# R3Mkr12F_MB.net
KiCad netlist of a schematic drawn in EAGLE
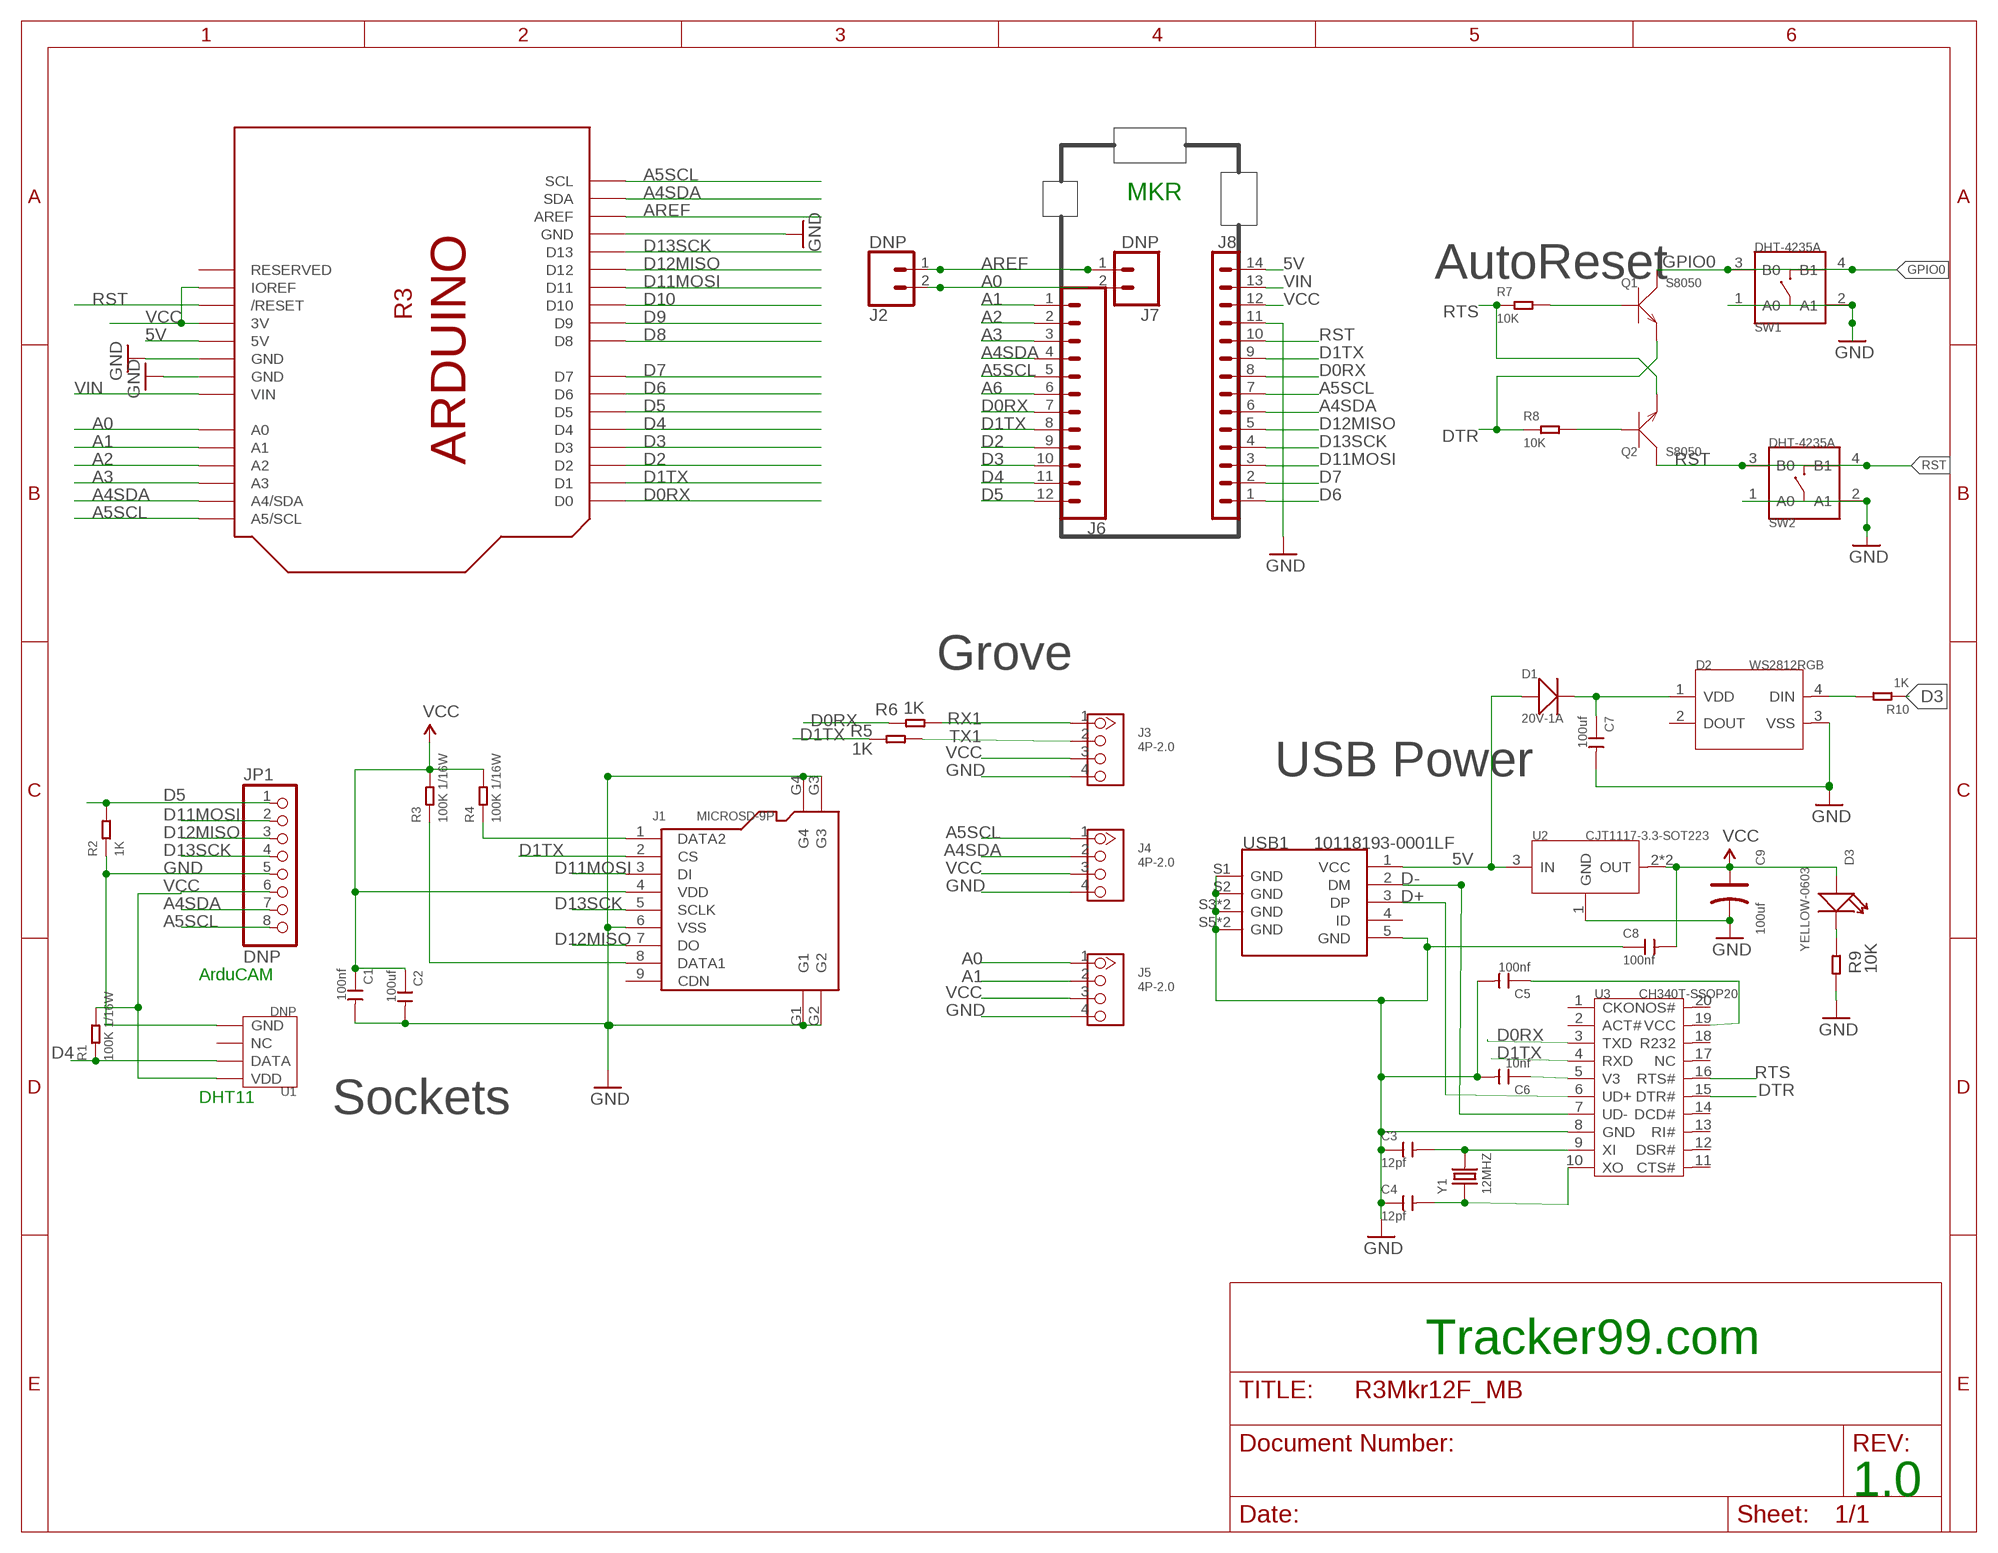
[diagram p0: schematic, sheet 1]

(export (version "E")
  (design (tool "Eeschema 10.0.6"))
  (components
    (comp (ref "C1")
      (value "100nf")
      (footprint "eagle-import:C0603")
      (fields (field (name "MPN") "CC0603KRX7R9BB104"))
      (libsource (lib "eagle-import") (part "CERAMIC-100NF-50V-10%-X7R(0603)"))
    )
    (comp (ref "C2")
      (value "100uf")
      (footprint "eagle-import:C1206")
      (fields (field (name "MPN") "GRM31CR60J107ME39L"))
      (libsource (lib "eagle-import") (part "CERAMIC-100UF-6.3V-20%-X5R(1206)"))
    )
    (comp (ref "C3")
      (value "12pf")
      (footprint "eagle-import:C0402")
      (fields (field (name "MPN") "CC0402JRNPO9BN120"))
      (libsource (lib "eagle-import") (part "CERAMIC-12PF-50V-5%-NPO(0402)"))
    )
    (comp (ref "C4")
      (value "12pf")
      (footprint "eagle-import:C0402")
      (fields (field (name "MPN") "CC0402JRNPO9BN120"))
      (libsource (lib "eagle-import") (part "CERAMIC-12PF-50V-5%-NPO(0402)"))
    )
    (comp (ref "C5")
      (value "100nf")
      (footprint "eagle-import:C0603")
      (fields (field (name "MPN") "CC0603KRX7R9BB104"))
      (libsource (lib "eagle-import") (part "CERAMIC-100NF-50V-10%-X7R(0603)"))
    )
    (comp (ref "C6")
      (value "10nf")
      (footprint "eagle-import:C0603")
      (fields (field (name "MPN") "CC0603KRX7R9BB103"))
      (libsource (lib "eagle-import") (part "CERAMIC-10NF-50V-10%-X7R(0603)"))
    )
    (comp (ref "C7")
      (value "100uf")
      (footprint "eagle-import:C1206")
      (fields (field (name "MPN") "GRM31CR60J107ME39L"))
      (libsource (lib "eagle-import") (part "CERAMIC-100UF-6.3V-20%-X5R(1206)"))
    )
    (comp (ref "C8")
      (value "100nf")
      (footprint "eagle-import:C0603")
      (fields (field (name "MPN") "CC0603KRX7R9BB104"))
      (libsource (lib "eagle-import") (part "CERAMIC-100NF-50V-10%-X7R(0603)"))
    )
    (comp (ref "C9")
      (value "100uf")
      (footprint "eagle-import:AVX-B")
      (fields (field (name "MPN") "TAJB107M010#NJ"))
      (libsource (lib "eagle-import") (part "TANTALUM-SMD-100UF-10V(AVX-B)"))
    )
    (comp (ref "D1")
      (value "20V-1A")
      (footprint "eagle-import:SOD-123")
      (fields (field (name "MPN") "B5819W"))
      (libsource (lib "eagle-import") (part "SMD-DIODE-SCHOTTKY-20V-1A(SOD-123)"))
    )
    (comp (ref "D2")
      (value "WS2812RGB")
      (footprint "eagle-import:LED4-SMD-5050")
      (libsource (lib "eagle-import") (part "SMD-RGB-LED-4P'WS2812B'"))
    )
    (comp (ref "D3")
      (value "YELLOW-0603")
      (footprint "eagle-import:LED-0603")
      (fields (field (name "MPN") "19-217-Y5C-AM1N1VY-3T"))
      (libsource (lib "eagle-import") (part "SMD-LED-CLEAR-YELLOW(0603)"))
    )
    (comp (ref "J1")
      (value "MICROSD-9P")
      (footprint "eagle-import:MICRO-SD9+4P-SMD-16.1X14.5X1.85MM")
      (libsource (lib "eagle-import") (part "MICRO-SD-CARD-HOLDER-9P"))
    )
    (comp (ref "J2")
      (value "DNP")
      (footprint "eagle-import:1X02")
      (libsource (lib "eagle-import") (part "CONN_02"))
    )
    (comp (ref "J3")
      (value "4P-2.0")
      (footprint "eagle-import:HW4-2.0")
      (libsource (lib "eagle-import") (part "GROVE-CONNECTOR-DIP(4P-2.0)"))
    )
    (comp (ref "J4")
      (value "4P-2.0")
      (footprint "eagle-import:HW4-2.0")
      (libsource (lib "eagle-import") (part "GROVE-CONNECTOR-DIP(4P-2.0)"))
    )
    (comp (ref "J5")
      (value "4P-2.0")
      (footprint "eagle-import:HW4-2.0")
      (libsource (lib "eagle-import") (part "GROVE-CONNECTOR-DIP(4P-2.0)"))
    )
    (comp (ref "J6")
      (value "CONN_12LOCK")
      (footprint "eagle-import:1X12_LOCK")
      (libsource (lib "eagle-import") (part "CONN_12LOCK"))
    )
    (comp (ref "J7")
      (value "DNP")
      (footprint "eagle-import:1X02")
      (libsource (lib "eagle-import") (part "CONN_02"))
    )
    (comp (ref "J8")
      (value "DNP")
      (footprint "eagle-import:1X14")
      (libsource (lib "eagle-import") (part "STRIP-14STD"))
    )
    (comp (ref "JP1")
      (value "DNP")
      (footprint "eagle-import:MILLER_1X08-LOCK")
      (libsource (lib "eagle-import") (part "MILLER_PINHD-1X8LOCK"))
    )
    (comp (ref "Q1")
      (value "S8050")
      (footprint "eagle-import:SOT-23")
      (libsource (lib "eagle-import") (part "SMD-TRANSISTORS-NPN-25V-500MW-S8050(SOT-23)"))
    )
    (comp (ref "Q2")
      (value "S8050")
      (footprint "eagle-import:SOT-23")
      (libsource (lib "eagle-import") (part "SMD-TRANSISTORS-NPN-25V-500MW-S8050(SOT-23)"))
    )
    (comp (ref "R1")
      (value "100K 1/16W")
      (footprint "eagle-import:R0402")
      (fields (field (name "MPN") "RC0402JR-07100KL"))
      (libsource (lib "eagle-import") (part "SMD-RES-100K-5%-1/16W(0402)"))
    )
    (comp (ref "R2")
      (value "1K")
      (footprint "eagle-import:R0805")
      (fields (field (name "MPN") "RC0805JR-071KL"))
      (libsource (lib "eagle-import") (part "SMD-RES-1K-5%-1/8W(0805)"))
    )
    (comp (ref "R3")
      (value "100K 1/16W")
      (footprint "eagle-import:R0402")
      (fields (field (name "MPN") "RC0402JR-07100KL"))
      (libsource (lib "eagle-import") (part "SMD-RES-100K-5%-1/16W(0402)"))
    )
    (comp (ref "R4")
      (value "100K 1/16W")
      (footprint "eagle-import:R0402")
      (fields (field (name "MPN") "RC0402JR-07100KL"))
      (libsource (lib "eagle-import") (part "SMD-RES-100K-5%-1/16W(0402)"))
    )
    (comp (ref "R5")
      (value "1K")
      (footprint "eagle-import:R0805")
      (fields (field (name "MPN") "RC0805JR-071KL"))
      (libsource (lib "eagle-import") (part "SMD-RES-1K-5%-1/8W(0805)"))
    )
    (comp (ref "R6")
      (value "1K")
      (footprint "eagle-import:R0805")
      (fields (field (name "MPN") "RC0805JR-071KL"))
      (libsource (lib "eagle-import") (part "SMD-RES-1K-5%-1/8W(0805)"))
    )
    (comp (ref "R7")
      (value "10K")
      (footprint "eagle-import:R0402")
      (fields (field (name "MPN") "RC0402JR-0710KL"))
      (libsource (lib "eagle-import") (part "SMD-RES-10K-5%-1/(0402)"))
    )
    (comp (ref "R8")
      (value "10K")
      (footprint "eagle-import:R0402")
      (fields (field (name "MPN") "RC0402JR-0710KL"))
      (libsource (lib "eagle-import") (part "SMD-RES-10K-5%-1/(0402)"))
    )
    (comp (ref "R9")
      (value "10K")
      (footprint "eagle-import:R0402")
      (fields (field (name "MPN") "RC0402JR-0710KL"))
      (libsource (lib "eagle-import") (part "SMD-RES-10K-5%-1/(0402)"))
    )
    (comp (ref "R10")
      (value "1K")
      (footprint "eagle-import:R0805")
      (fields (field (name "MPN") "RC0805JR-071KL"))
      (libsource (lib "eagle-import") (part "SMD-RES-1K-5%-1/8W(0805)"))
    )
    (comp (ref "SW1")
      (value "DHT-4235A")
      (footprint "eagle-import:SW4-SMD-4.2X3.2X2.5MM")
      (libsource (lib "eagle-import") (part "SMD-BUTTON-TOP-DHT-4235A(4P-4.2X3.2MM)"))
    )
    (comp (ref "SW2")
      (value "DHT-4235A")
      (footprint "eagle-import:SW4-SMD-4.2X3.2X2.5MM")
      (libsource (lib "eagle-import") (part "SMD-BUTTON-TOP-DHT-4235A(4P-4.2X3.2MM)"))
    )
    (comp (ref "U1")
      (value "DNP")
      (footprint "eagle-import:SNR4-2.54-15.5X12.0X5.5MM")
      (fields (field (name "MPN") "DHT11"))
      (libsource (lib "eagle-import") (part "TEM-HUM-DHT11(4P-15.5X12.0MM)"))
    )
    (comp (ref "U2")
      (value "CJT1117-3.3-SOT223")
      (footprint "eagle-import:SOT-223")
      (fields (field (name "MPN") "CJT1117-3.3"))
      (libsource (lib "eagle-import") (part "PMIC-CJT1117-3.3(SOT223)"))
    )
    (comp (ref "U3")
      (value "CH340T-SSOP20")
      (footprint "eagle-import:SSOP20-0.65-7.6X5.2MM")
      (fields (field (name "MPN") "CH340T"))
      (libsource (lib "eagle-import") (part "INTERFACE-CH340T(SSOP20)"))
    )
    (comp (ref "UNO1")
      (value "MKR12FUNO99_ARDUINO_R3_NOICSP_47MM")
      (footprint "eagle-import:MKR12FUNO99_ARDUINOR3_NOICSP_47MM")
      (libsource (lib "eagle-import") (part "MKR12FUNO99_ARDUINO_R3_NOICSP_47MM"))
    )
    (comp (ref "USB1")
      (value "10118193-0001LF")
      (footprint "eagle-import:MICRO-USB5+6P-SMD-0.65-B")
      (libsource (lib "eagle-import") (part "MICRO-USB-SMD-B-(10118193-0001LF)"))
    )
    (comp (ref "Y1")
      (value "12MHZ")
      (footprint "eagle-import:X2-SMD-5.0X3.2X1.3MM")
      (fields (field (name "MPN") "5032/2P"))
      (libsource (lib "eagle-import") (part "SMD-CRYSTAL-12MHZ-20PF-20PPM-40R(2P-5.0X3.2MM)"))
    )
  )
  (nets
    (net (code "1") (name "/5V") (class "Default")
      (node (ref "D1") (pin "+") (pinfunction "+_+") (pintype "passive"))
      (node (ref "J8") (pin "14") (pinfunction "14_14") (pintype "passive"))
      (node (ref "U2") (pin "3") (pinfunction "IN_3") (pintype "bidirectional"))
      (node (ref "UNO1") (pin "5V") (pinfunction "5V_5V") (pintype "power_in"))
      (node (ref "USB1") (pin "1") (pinfunction "VCC_1") (pintype "bidirectional"))
    )
    (net (code "2") (name "/A0") (class "Default")
      (node (ref "J2") (pin "2") (pinfunction "2_2") (pintype "passive"))
      (node (ref "J5") (pin "1") (pinfunction "1_1") (pintype "bidirectional"))
      (node (ref "J7") (pin "2") (pinfunction "2_2") (pintype "passive"))
      (node (ref "UNO1") (pin "A0") (pinfunction "A0_A0") (pintype "bidirectional"))
    )
    (net (code "3") (name "/A1") (class "Default")
      (node (ref "J5") (pin "2") (pinfunction "2_2") (pintype "bidirectional"))
      (node (ref "J6") (pin "1") (pinfunction "1_1") (pintype "passive"))
      (node (ref "UNO1") (pin "A1") (pinfunction "A1_A1") (pintype "bidirectional"))
    )
    (net (code "4") (name "/A2") (class "Default")
      (node (ref "J6") (pin "2") (pinfunction "2_2") (pintype "passive"))
      (node (ref "UNO1") (pin "A2") (pinfunction "A2_A2") (pintype "bidirectional"))
    )
    (net (code "5") (name "/A3") (class "Default")
      (node (ref "J6") (pin "3") (pinfunction "3_3") (pintype "passive"))
      (node (ref "UNO1") (pin "A3") (pinfunction "A3_A3") (pintype "bidirectional"))
    )
    (net (code "6") (name "/A4SDA") (class "Default")
      (node (ref "J4") (pin "2") (pinfunction "2_2") (pintype "bidirectional"))
      (node (ref "J6") (pin "4") (pinfunction "4_4") (pintype "passive"))
      (node (ref "J8") (pin "6") (pinfunction "6_6") (pintype "passive"))
      (node (ref "JP1") (pin "7") (pinfunction "7_7") (pintype "passive"))
      (node (ref "UNO1") (pin "A4") (pinfunction "A4/SDA_A4") (pintype "bidirectional"))
      (node (ref "UNO1") (pin "SDA") (pinfunction "SDA_SDA") (pintype "bidirectional"))
    )
    (net (code "7") (name "/A5SCL") (class "Default")
      (node (ref "J4") (pin "1") (pinfunction "1_1") (pintype "bidirectional"))
      (node (ref "J6") (pin "5") (pinfunction "5_5") (pintype "passive"))
      (node (ref "J8") (pin "7") (pinfunction "7_7") (pintype "passive"))
      (node (ref "JP1") (pin "8") (pinfunction "8_8") (pintype "passive"))
      (node (ref "UNO1") (pin "A5") (pinfunction "A5/SCL_A5") (pintype "bidirectional"))
      (node (ref "UNO1") (pin "SCL") (pinfunction "SCL_SCL") (pintype "bidirectional"))
    )
    (net (code "8") (name "/A6") (class "Default")
      (node (ref "J6") (pin "6") (pinfunction "6_6") (pintype "passive"))
    )
    (net (code "9") (name "/AREF") (class "Default")
      (node (ref "J2") (pin "1") (pinfunction "1_1") (pintype "passive"))
      (node (ref "J7") (pin "1") (pinfunction "1_1") (pintype "passive"))
      (node (ref "UNO1") (pin "AREF") (pinfunction "AREF_AREF") (pintype "bidirectional"))
    )
    (net (code "10") (name "/D+") (class "Default")
      (node (ref "U3") (pin "6") (pinfunction "UD+_6") (pintype "bidirectional"))
      (node (ref "USB1") (pin "3") (pinfunction "DP_3") (pintype "bidirectional"))
    )
    (net (code "11") (name "/D-") (class "Default")
      (node (ref "U3") (pin "7") (pinfunction "UD-_7") (pintype "bidirectional"))
      (node (ref "USB1") (pin "2") (pinfunction "DM_2") (pintype "bidirectional"))
    )
    (net (code "12") (name "/D0RX") (class "Default")
      (node (ref "J6") (pin "7") (pinfunction "7_7") (pintype "passive"))
      (node (ref "J8") (pin "8") (pinfunction "8_8") (pintype "passive"))
      (node (ref "R6") (pin "2") (pinfunction "2_2") (pintype "passive"))
      (node (ref "U3") (pin "3") (pinfunction "TXD_3") (pintype "output"))
      (node (ref "UNO1") (pin "D0") (pinfunction "D0_D0") (pintype "bidirectional"))
    )
    (net (code "13") (name "/D1TX") (class "Default")
      (node (ref "J1") (pin "2") (pinfunction "CS_2") (pintype "bidirectional"))
      (node (ref "J6") (pin "8") (pinfunction "8_8") (pintype "passive"))
      (node (ref "J8") (pin "9") (pinfunction "9_9") (pintype "passive"))
      (node (ref "R5") (pin "2") (pinfunction "2_2") (pintype "passive"))
      (node (ref "U3") (pin "4") (pinfunction "RXD_4") (pintype "input"))
      (node (ref "UNO1") (pin "D1") (pinfunction "D1_D1") (pintype "bidirectional"))
    )
    (net (code "14") (name "/D2") (class "Default")
      (node (ref "J6") (pin "9") (pinfunction "9_9") (pintype "passive"))
      (node (ref "UNO1") (pin "D2") (pinfunction "D2_D2") (pintype "bidirectional"))
    )
    (net (code "15") (name "/D4") (class "Default")
      (node (ref "J6") (pin "11") (pinfunction "11_11") (pintype "passive"))
      (node (ref "R1") (pin "1") (pinfunction "1_1") (pintype "passive"))
      (node (ref "U1") (pin "2") (pinfunction "DATA_2") (pintype "bidirectional"))
      (node (ref "UNO1") (pin "D4") (pinfunction "D4_D4") (pintype "bidirectional"))
    )
    (net (code "16") (name "/D5") (class "Default")
      (node (ref "J6") (pin "12") (pinfunction "12_12") (pintype "passive"))
      (node (ref "JP1") (pin "1") (pinfunction "1_1") (pintype "passive"))
      (node (ref "R2") (pin "2") (pinfunction "2_2") (pintype "passive"))
      (node (ref "UNO1") (pin "D5") (pinfunction "D5_D5") (pintype "bidirectional"))
    )
    (net (code "17") (name "/D6") (class "Default")
      (node (ref "J8") (pin "1") (pinfunction "1_1") (pintype "passive"))
      (node (ref "UNO1") (pin "D6") (pinfunction "D6_D6") (pintype "bidirectional"))
    )
    (net (code "18") (name "/D7") (class "Default")
      (node (ref "J8") (pin "2") (pinfunction "2_2") (pintype "passive"))
      (node (ref "UNO1") (pin "D7") (pinfunction "D7_D7") (pintype "bidirectional"))
    )
    (net (code "19") (name "/D8") (class "Default")
      (node (ref "UNO1") (pin "D8") (pinfunction "D8_D8") (pintype "bidirectional"))
    )
    (net (code "20") (name "/D9") (class "Default")
      (node (ref "UNO1") (pin "D9") (pinfunction "D9_D9") (pintype "bidirectional"))
    )
    (net (code "21") (name "/D10") (class "Default")
      (node (ref "UNO1") (pin "D10") (pinfunction "D10_D10") (pintype "bidirectional"))
    )
    (net (code "22") (name "/D11MOSI") (class "Default")
      (node (ref "J1") (pin "3") (pinfunction "DI_3") (pintype "bidirectional"))
      (node (ref "J8") (pin "3") (pinfunction "3_3") (pintype "passive"))
      (node (ref "JP1") (pin "2") (pinfunction "2_2") (pintype "passive"))
      (node (ref "UNO1") (pin "D11") (pinfunction "D11_D11") (pintype "bidirectional"))
    )
    (net (code "23") (name "/D12MISO") (class "Default")
      (node (ref "J1") (pin "7") (pinfunction "DO_7") (pintype "bidirectional"))
      (node (ref "J8") (pin "5") (pinfunction "5_5") (pintype "passive"))
      (node (ref "JP1") (pin "3") (pinfunction "3_3") (pintype "passive"))
      (node (ref "UNO1") (pin "D12") (pinfunction "D12_D12") (pintype "bidirectional"))
    )
    (net (code "24") (name "/D13SCK") (class "Default")
      (node (ref "J1") (pin "5") (pinfunction "SCLK_5") (pintype "bidirectional"))
      (node (ref "J8") (pin "4") (pinfunction "4_4") (pintype "passive"))
      (node (ref "JP1") (pin "4") (pinfunction "4_4") (pintype "passive"))
      (node (ref "UNO1") (pin "D13") (pinfunction "D13_D13") (pintype "bidirectional"))
    )
    (net (code "25") (name "/DTR") (class "Default")
      (node (ref "Q1") (pin "2") (pinfunction "E_2") (pintype "passive"))
      (node (ref "R8") (pin "1") (pinfunction "1_1") (pintype "passive"))
      (node (ref "U3") (pin "15") (pinfunction "DTR#_15") (pintype "output"))
    )
    (net (code "26") (name "/NOS#") (class "Default")
      (node (ref "U3") (pin "20") (pinfunction "NOS#_20") (pintype "power_in"))
    )
    (net (code "27") (name "/RTS") (class "Default")
      (node (ref "Q2") (pin "2") (pinfunction "E_2") (pintype "passive"))
      (node (ref "R7") (pin "1") (pinfunction "1_1") (pintype "passive"))
      (node (ref "U3") (pin "16") (pinfunction "RTS#_16") (pintype "output"))
    )
    (net (code "28") (name "/RX1") (class "Default")
      (node (ref "J3") (pin "1") (pinfunction "1_1") (pintype "bidirectional"))
      (node (ref "R6") (pin "1") (pinfunction "1_1") (pintype "passive"))
    )
    (net (code "29") (name "/TX1") (class "Default")
      (node (ref "J3") (pin "2") (pinfunction "2_2") (pintype "bidirectional"))
      (node (ref "R5") (pin "1") (pinfunction "1_1") (pintype "passive"))
    )
    (net (code "30") (name "/VIN") (class "Default")
      (node (ref "J8") (pin "13") (pinfunction "13_13") (pintype "passive"))
      (node (ref "UNO1") (pin "VIN") (pinfunction "VIN_VIN") (pintype "power_in"))
    )
    (net (code "31") (name "D3") (class "Default")
      (node (ref "J6") (pin "10") (pinfunction "10_10") (pintype "passive"))
      (node (ref "R10") (pin "1") (pinfunction "1_1") (pintype "passive"))
      (node (ref "UNO1") (pin "D3") (pinfunction "D3_D3") (pintype "bidirectional"))
    )
    (net (code "32") (name "GND") (class "Default")
      (node (ref "C1") (pin "2") (pinfunction "2_2") (pintype "passive"))
      (node (ref "C2") (pin "2") (pinfunction "2_2") (pintype "passive"))
      (node (ref "C3") (pin "1") (pinfunction "1_1") (pintype "passive"))
      (node (ref "C4") (pin "1") (pinfunction "1_1") (pintype "passive"))
      (node (ref "C5") (pin "2") (pinfunction "2_2") (pintype "passive"))
      (node (ref "C6") (pin "2") (pinfunction "2_2") (pintype "passive"))
      (node (ref "C7") (pin "2") (pinfunction "2_2") (pintype "passive"))
      (node (ref "C8") (pin "1") (pinfunction "1_1") (pintype "passive"))
      (node (ref "C9") (pin "-") (pinfunction "-_-") (pintype "passive"))
      (node (ref "D2") (pin "3") (pinfunction "VSS_3") (pintype "bidirectional"))
      (node (ref "J1") (pin "6") (pinfunction "VSS_6") (pintype "bidirectional"))
      (node (ref "J1") (pin "G1") (pinfunction "G1_G1") (pintype "bidirectional"))
      (node (ref "J1") (pin "G2") (pinfunction "G2_G2") (pintype "bidirectional"))
      (node (ref "J1") (pin "G3") (pinfunction "G3_G3") (pintype "bidirectional"))
      (node (ref "J1") (pin "G4") (pinfunction "G4_G4") (pintype "bidirectional"))
      (node (ref "J3") (pin "4") (pinfunction "4_4") (pintype "bidirectional"))
      (node (ref "J4") (pin "4") (pinfunction "4_4") (pintype "bidirectional"))
      (node (ref "J5") (pin "4") (pinfunction "4_4") (pintype "bidirectional"))
      (node (ref "J8") (pin "11") (pinfunction "11_11") (pintype "passive"))
      (node (ref "JP1") (pin "5") (pinfunction "5_5") (pintype "passive"))
      (node (ref "R2") (pin "1") (pinfunction "1_1") (pintype "passive"))
      (node (ref "R9") (pin "1") (pinfunction "1_1") (pintype "passive"))
      (node (ref "SW1") (pin "1") (pinfunction "A0_1") (pintype "bidirectional"))
      (node (ref "SW1") (pin "2") (pinfunction "A1_2") (pintype "bidirectional"))
      (node (ref "SW2") (pin "1") (pinfunction "A0_1") (pintype "bidirectional"))
      (node (ref "SW2") (pin "2") (pinfunction "A1_2") (pintype "bidirectional"))
      (node (ref "U1") (pin "4") (pinfunction "GND_4") (pintype "power_in"))
      (node (ref "U2") (pin "1") (pinfunction "GND_1") (pintype "bidirectional"))
      (node (ref "U3") (pin "8") (pinfunction "GND_8") (pintype "power_in"))
      (node (ref "UNO1") (pin "GND") (pinfunction "GND_GND") (pintype "power_in"))
      (node (ref "UNO1") (pin "GND@1") (pinfunction "GND_GND@1") (pintype "power_in"))
      (node (ref "UNO1") (pin "GND@2") (pinfunction "GND_GND@2") (pintype "power_in"))
      (node (ref "USB1") (pin "5") (pinfunction "GND_5") (pintype "bidirectional"))
      (node (ref "USB1") (pin "S1") (pinfunction "GND_S1") (pintype "bidirectional"))
      (node (ref "USB1") (pin "S2") (pinfunction "GND_S2") (pintype "bidirectional"))
      (node (ref "USB1") (pin "S3") (pinfunction "GND_S3") (pintype "bidirectional"))
      (node (ref "USB1") (pin "S4") (pinfunction "GND_S4") (pintype "bidirectional"))
      (node (ref "USB1") (pin "S5") (pinfunction "GND_S5") (pintype "bidirectional"))
      (node (ref "USB1") (pin "S6") (pinfunction "GND_S6") (pintype "bidirectional"))
    )
    (net (code "33") (name "GPIO0") (class "Default")
      (node (ref "Q1") (pin "3") (pinfunction "C_3") (pintype "passive"))
      (node (ref "SW1") (pin "3") (pinfunction "B0_3") (pintype "bidirectional"))
      (node (ref "SW1") (pin "4") (pinfunction "B1_4") (pintype "bidirectional"))
    )
    (net (code "34") (name "Net-(D2-DIN)") (class "Default")
      (node (ref "D2") (pin "4") (pinfunction "DIN_4") (pintype "bidirectional"))
      (node (ref "R10") (pin "2") (pinfunction "2_2") (pintype "passive"))
    )
    (net (code "35") (name "Net-(D2-VDD)") (class "Default")
      (node (ref "C7") (pin "1") (pinfunction "1_1") (pintype "passive"))
      (node (ref "D1") (pin "-") (pinfunction "-_-") (pintype "passive"))
      (node (ref "D2") (pin "1") (pinfunction "VDD_1") (pintype "bidirectional"))
    )
    (net (code "36") (name "Net-(D3-Pad-)") (class "Default")
      (node (ref "D3") (pin "-") (pinfunction "-_-") (pintype "passive"))
      (node (ref "R9") (pin "2") (pinfunction "2_2") (pintype "passive"))
    )
    (net (code "37") (name "Net-(J1-DATA1)") (class "Default")
      (node (ref "J1") (pin "8") (pinfunction "DATA1_8") (pintype "bidirectional"))
      (node (ref "R3") (pin "1") (pinfunction "1_1") (pintype "passive"))
    )
    (net (code "38") (name "Net-(J1-DATA2)") (class "Default")
      (node (ref "J1") (pin "1") (pinfunction "DATA2_1") (pintype "bidirectional"))
      (node (ref "R4") (pin "1") (pinfunction "1_1") (pintype "passive"))
    )
    (net (code "39") (name "Net-(Q1-B)") (class "Default")
      (node (ref "Q1") (pin "1") (pinfunction "B_1") (pintype "passive"))
      (node (ref "R7") (pin "2") (pinfunction "2_2") (pintype "passive"))
    )
    (net (code "40") (name "Net-(Q2-B)") (class "Default")
      (node (ref "Q2") (pin "1") (pinfunction "B_1") (pintype "passive"))
      (node (ref "R8") (pin "2") (pinfunction "2_2") (pintype "passive"))
    )
    (net (code "41") (name "Net-(U3-V3)") (class "Default")
      (node (ref "C6") (pin "1") (pinfunction "1_1") (pintype "passive"))
      (node (ref "U3") (pin "5") (pinfunction "V3_5") (pintype "power_in"))
    )
    (net (code "42") (name "Net-(U3-XI)") (class "Default")
      (node (ref "C3") (pin "2") (pinfunction "2_2") (pintype "passive"))
      (node (ref "U3") (pin "9") (pinfunction "XI_9") (pintype "input"))
      (node (ref "Y1") (pin "2") (pinfunction "2_2") (pintype "passive"))
    )
    (net (code "43") (name "Net-(U3-XO)") (class "Default")
      (node (ref "C4") (pin "2") (pinfunction "2_2") (pintype "passive"))
      (node (ref "U3") (pin "10") (pinfunction "XO_10") (pintype "output"))
      (node (ref "Y1") (pin "1") (pinfunction "1_1") (pintype "passive"))
    )
    (net (code "44") (name "RST") (class "Default")
      (node (ref "J8") (pin "10") (pinfunction "10_10") (pintype "passive"))
      (node (ref "Q2") (pin "3") (pinfunction "C_3") (pintype "passive"))
      (node (ref "SW2") (pin "3") (pinfunction "B0_3") (pintype "bidirectional"))
      (node (ref "SW2") (pin "4") (pinfunction "B1_4") (pintype "bidirectional"))
      (node (ref "UNO1") (pin "RESET") (pinfunction "/RESET_RESET") (pintype "bidirectional"))
    )
    (net (code "45") (name "VCC") (class "Default")
      (node (ref "C1") (pin "1") (pinfunction "1_1") (pintype "passive"))
      (node (ref "C2") (pin "1") (pinfunction "1_1") (pintype "passive"))
      (node (ref "C5") (pin "1") (pinfunction "1_1") (pintype "passive"))
      (node (ref "C8") (pin "2") (pinfunction "2_2") (pintype "passive"))
      (node (ref "C9") (pin "+") (pinfunction "+_+") (pintype "passive"))
      (node (ref "D3") (pin "+") (pinfunction "+_+") (pintype "passive"))
      (node (ref "J1") (pin "4") (pinfunction "VDD_4") (pintype "bidirectional"))
      (node (ref "J3") (pin "3") (pinfunction "3_3") (pintype "bidirectional"))
      (node (ref "J4") (pin "3") (pinfunction "3_3") (pintype "bidirectional"))
      (node (ref "J5") (pin "3") (pinfunction "3_3") (pintype "bidirectional"))
      (node (ref "J8") (pin "12") (pinfunction "12_12") (pintype "passive"))
      (node (ref "JP1") (pin "6") (pinfunction "6_6") (pintype "passive"))
      (node (ref "R1") (pin "2") (pinfunction "2_2") (pintype "passive"))
      (node (ref "R3") (pin "2") (pinfunction "2_2") (pintype "passive"))
      (node (ref "R4") (pin "2") (pinfunction "2_2") (pintype "passive"))
      (node (ref "U1") (pin "1") (pinfunction "VDD_1") (pintype "power_in"))
      (node (ref "U2") (pin "2") (pinfunction "OUT_2") (pintype "bidirectional"))
      (node (ref "U2") (pin "TER") (pinfunction "OUT_TER") (pintype "bidirectional"))
      (node (ref "U3") (pin "19") (pinfunction "VCC_19") (pintype "power_in"))
      (node (ref "UNO1") (pin "3V") (pinfunction "3V_3V") (pintype "power_in"))
      (node (ref "UNO1") (pin "IOREF") (pinfunction "IOREF_IOREF") (pintype "output"))
    )
    (net (code "46") (name "unconnected-(D2-DOUT-Pad2)") (class "Default")
      (node (ref "D2") (pin "2") (pinfunction "DOUT_2") (pintype "bidirectional"))
    )
    (net (code "47") (name "unconnected-(J1-CDN-Pad9)") (class "Default")
      (node (ref "J1") (pin "9") (pinfunction "CDN_9") (pintype "bidirectional"))
    )
    (net (code "48") (name "unconnected-(U1-NC-Pad3)") (class "Default")
      (node (ref "U1") (pin "3") (pinfunction "NC_3") (pintype "no_connect"))
    )
    (net (code "49") (name "unconnected-(U3-ACT#-Pad2)") (class "Default")
      (node (ref "U3") (pin "2") (pinfunction "ACT#_2") (pintype "output"))
    )
    (net (code "50") (name "unconnected-(U3-CKO-Pad1)") (class "Default")
      (node (ref "U3") (pin "1") (pinfunction "CKO_1") (pintype "output"))
    )
    (net (code "51") (name "unconnected-(U3-CTS#-Pad11)") (class "Default")
      (node (ref "U3") (pin "11") (pinfunction "CTS#_11") (pintype "input"))
    )
    (net (code "52") (name "unconnected-(U3-DCD#-Pad14)") (class "Default")
      (node (ref "U3") (pin "14") (pinfunction "DCD#_14") (pintype "input"))
    )
    (net (code "53") (name "unconnected-(U3-DSR#-Pad12)") (class "Default")
      (node (ref "U3") (pin "12") (pinfunction "DSR#_12") (pintype "input"))
    )
    (net (code "54") (name "unconnected-(U3-NC-Pad17)") (class "Default")
      (node (ref "U3") (pin "17") (pinfunction "NC_17") (pintype "no_connect"))
    )
    (net (code "55") (name "unconnected-(U3-R232-Pad18)") (class "Default")
      (node (ref "U3") (pin "18") (pinfunction "R232_18") (pintype "input"))
    )
    (net (code "56") (name "unconnected-(U3-RI#-Pad13)") (class "Default")
      (node (ref "U3") (pin "13") (pinfunction "RI#_13") (pintype "input"))
    )
    (net (code "57") (name "unconnected-(UNO1-PadRESERVED)") (class "Default")
      (node (ref "UNO1") (pin "RESERVED") (pinfunction "RESERVED_RESERVED") (pintype "no_connect"))
    )
    (net (code "58") (name "unconnected-(USB1-ID-Pad4)") (class "Default")
      (node (ref "USB1") (pin "4") (pinfunction "ID_4") (pintype "bidirectional"))
    )
  )
)
